# M906A.net
KiCad netlist of a schematic drawn in EAGLE
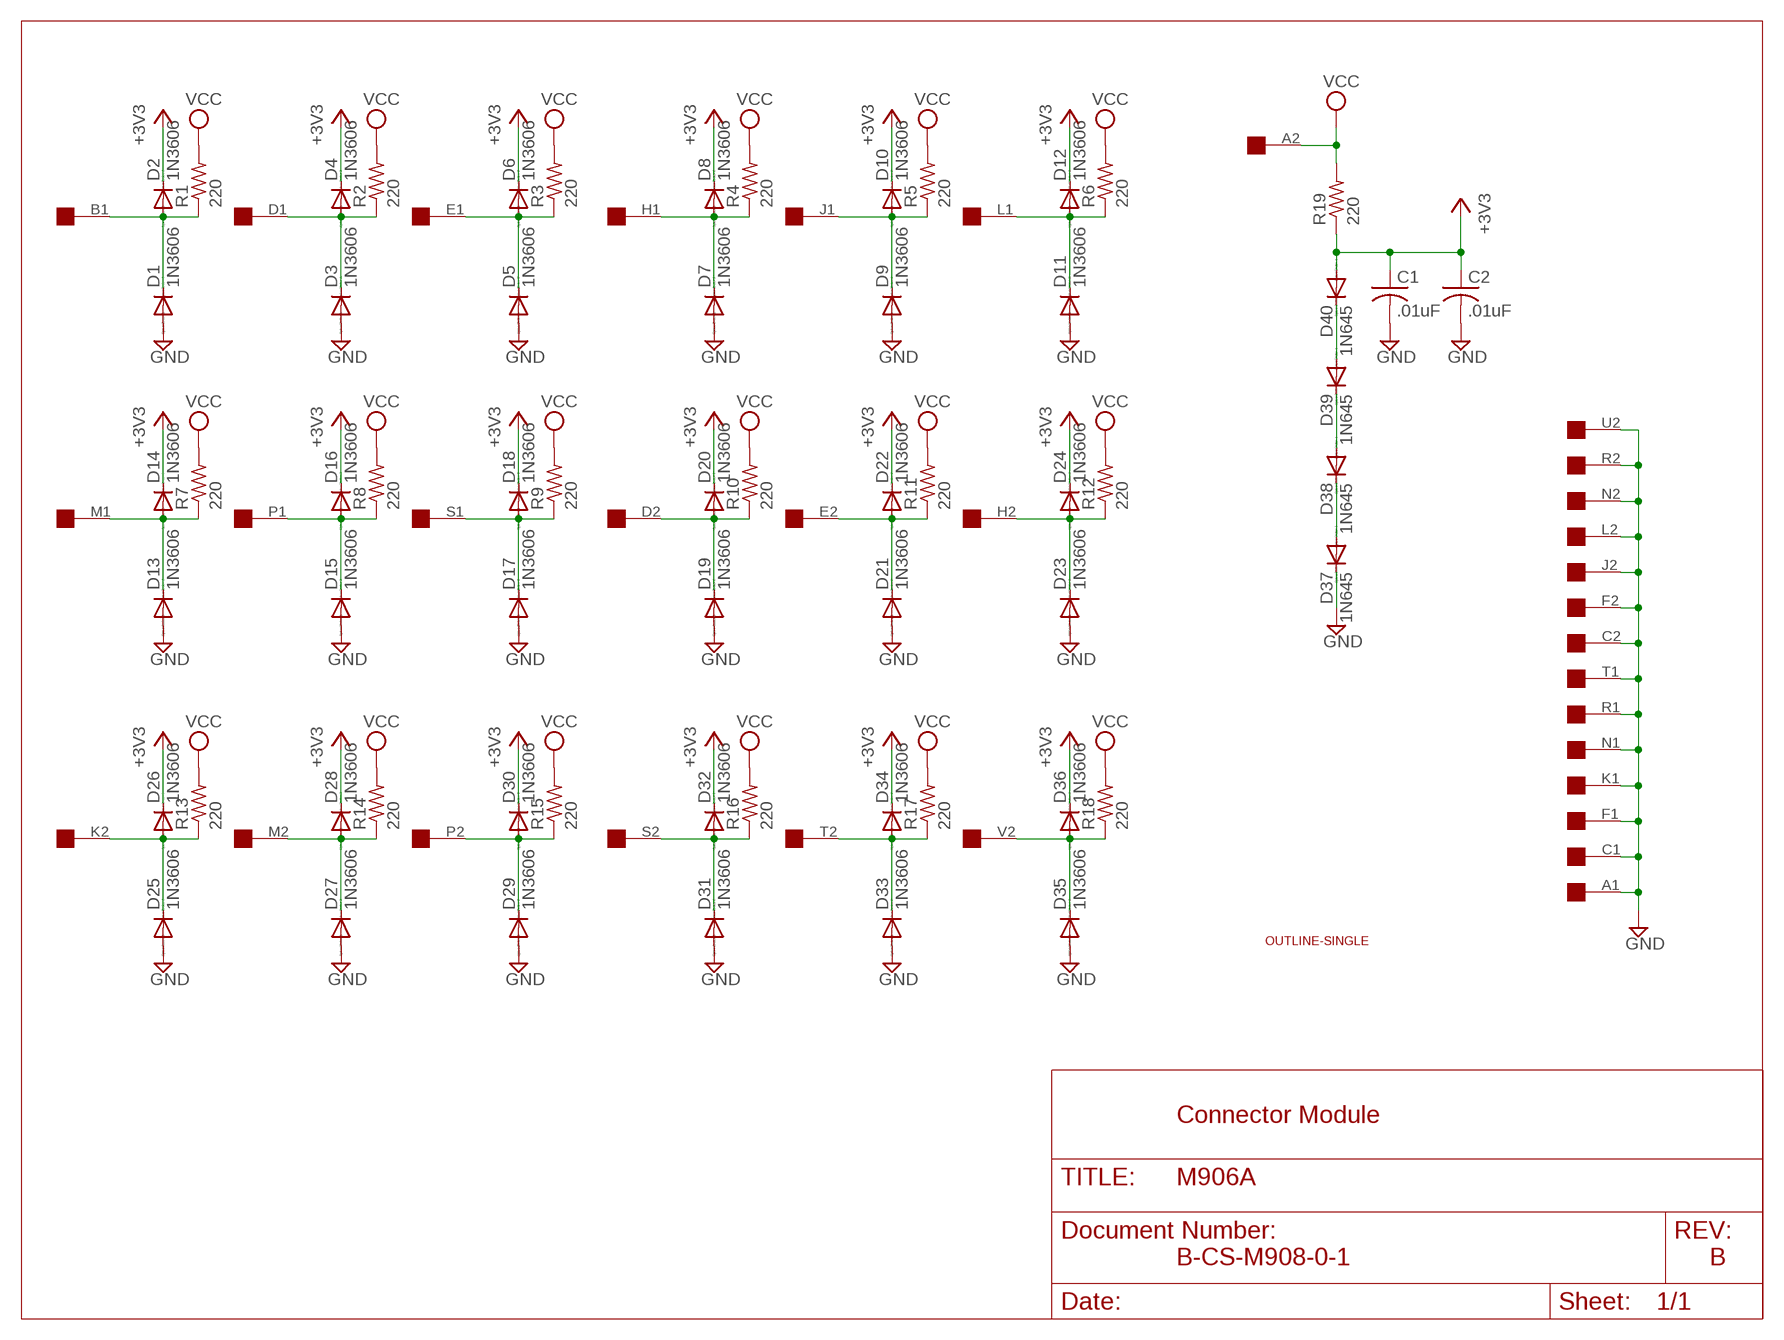
[diagram p0: schematic, sheet 1]

(export (version "E")
  (design (tool "Eeschema 10.0.6"))
  (components
    (comp (ref "C1")
      (value ".01uF")
      (footprint "eagle-import:C050-025X075")
      (libsource (lib "eagle-import") (part "C-US050-025X075"))
    )
    (comp (ref "C2")
      (value ".01uF")
      (footprint "eagle-import:C050-025X075")
      (libsource (lib "eagle-import") (part "C-US050-025X075"))
    )
    (comp (ref "D1")
      (value "1N3606")
      (footprint "eagle-import:DO35-10")
      (libsource (lib "eagle-import") (part "1N4148DO35-10"))
    )
    (comp (ref "D2")
      (value "1N3606")
      (footprint "eagle-import:DO35-10")
      (libsource (lib "eagle-import") (part "1N4148DO35-10"))
    )
    (comp (ref "D3")
      (value "1N3606")
      (footprint "eagle-import:DO35-10")
      (libsource (lib "eagle-import") (part "1N4148DO35-10"))
    )
    (comp (ref "D4")
      (value "1N3606")
      (footprint "eagle-import:DO35-10")
      (libsource (lib "eagle-import") (part "1N4148DO35-10"))
    )
    (comp (ref "D5")
      (value "1N3606")
      (footprint "eagle-import:DO35-10")
      (libsource (lib "eagle-import") (part "1N4148DO35-10"))
    )
    (comp (ref "D6")
      (value "1N3606")
      (footprint "eagle-import:DO35-10")
      (libsource (lib "eagle-import") (part "1N4148DO35-10"))
    )
    (comp (ref "D7")
      (value "1N3606")
      (footprint "eagle-import:DO35-10")
      (libsource (lib "eagle-import") (part "1N4148DO35-10"))
    )
    (comp (ref "D8")
      (value "1N3606")
      (footprint "eagle-import:DO35-10")
      (libsource (lib "eagle-import") (part "1N4148DO35-10"))
    )
    (comp (ref "D9")
      (value "1N3606")
      (footprint "eagle-import:DO35-10")
      (libsource (lib "eagle-import") (part "1N4148DO35-10"))
    )
    (comp (ref "D10")
      (value "1N3606")
      (footprint "eagle-import:DO35-10")
      (libsource (lib "eagle-import") (part "1N4148DO35-10"))
    )
    (comp (ref "D11")
      (value "1N3606")
      (footprint "eagle-import:DO35-10")
      (libsource (lib "eagle-import") (part "1N4148DO35-10"))
    )
    (comp (ref "D12")
      (value "1N3606")
      (footprint "eagle-import:DO35-10")
      (libsource (lib "eagle-import") (part "1N4148DO35-10"))
    )
    (comp (ref "D13")
      (value "1N3606")
      (footprint "eagle-import:DO35-10")
      (libsource (lib "eagle-import") (part "1N4148DO35-10"))
    )
    (comp (ref "D14")
      (value "1N3606")
      (footprint "eagle-import:DO35-10")
      (libsource (lib "eagle-import") (part "1N4148DO35-10"))
    )
    (comp (ref "D15")
      (value "1N3606")
      (footprint "eagle-import:DO35-10")
      (libsource (lib "eagle-import") (part "1N4148DO35-10"))
    )
    (comp (ref "D16")
      (value "1N3606")
      (footprint "eagle-import:DO35-10")
      (libsource (lib "eagle-import") (part "1N4148DO35-10"))
    )
    (comp (ref "D17")
      (value "1N3606")
      (footprint "eagle-import:DO35-10")
      (libsource (lib "eagle-import") (part "1N4148DO35-10"))
    )
    (comp (ref "D18")
      (value "1N3606")
      (footprint "eagle-import:DO35-10")
      (libsource (lib "eagle-import") (part "1N4148DO35-10"))
    )
    (comp (ref "D19")
      (value "1N3606")
      (footprint "eagle-import:DO35-10")
      (libsource (lib "eagle-import") (part "1N4148DO35-10"))
    )
    (comp (ref "D20")
      (value "1N3606")
      (footprint "eagle-import:DO35-10")
      (libsource (lib "eagle-import") (part "1N4148DO35-10"))
    )
    (comp (ref "D21")
      (value "1N3606")
      (footprint "eagle-import:DO35-10")
      (libsource (lib "eagle-import") (part "1N4148DO35-10"))
    )
    (comp (ref "D22")
      (value "1N3606")
      (footprint "eagle-import:DO35-10")
      (libsource (lib "eagle-import") (part "1N4148DO35-10"))
    )
    (comp (ref "D23")
      (value "1N3606")
      (footprint "eagle-import:DO35-10")
      (libsource (lib "eagle-import") (part "1N4148DO35-10"))
    )
    (comp (ref "D24")
      (value "1N3606")
      (footprint "eagle-import:DO35-10")
      (libsource (lib "eagle-import") (part "1N4148DO35-10"))
    )
    (comp (ref "D25")
      (value "1N3606")
      (footprint "eagle-import:DO35-10")
      (libsource (lib "eagle-import") (part "1N4148DO35-10"))
    )
    (comp (ref "D26")
      (value "1N3606")
      (footprint "eagle-import:DO35-10")
      (libsource (lib "eagle-import") (part "1N4148DO35-10"))
    )
    (comp (ref "D27")
      (value "1N3606")
      (footprint "eagle-import:DO35-10")
      (libsource (lib "eagle-import") (part "1N4148DO35-10"))
    )
    (comp (ref "D28")
      (value "1N3606")
      (footprint "eagle-import:DO35-10")
      (libsource (lib "eagle-import") (part "1N4148DO35-10"))
    )
    (comp (ref "D29")
      (value "1N3606")
      (footprint "eagle-import:DO35-10")
      (libsource (lib "eagle-import") (part "1N4148DO35-10"))
    )
    (comp (ref "D30")
      (value "1N3606")
      (footprint "eagle-import:DO35-10")
      (libsource (lib "eagle-import") (part "1N4148DO35-10"))
    )
    (comp (ref "D31")
      (value "1N3606")
      (footprint "eagle-import:DO35-10")
      (libsource (lib "eagle-import") (part "1N4148DO35-10"))
    )
    (comp (ref "D32")
      (value "1N3606")
      (footprint "eagle-import:DO35-10")
      (libsource (lib "eagle-import") (part "1N4148DO35-10"))
    )
    (comp (ref "D33")
      (value "1N3606")
      (footprint "eagle-import:DO35-10")
      (libsource (lib "eagle-import") (part "1N4148DO35-10"))
    )
    (comp (ref "D34")
      (value "1N3606")
      (footprint "eagle-import:DO35-10")
      (libsource (lib "eagle-import") (part "1N4148DO35-10"))
    )
    (comp (ref "D35")
      (value "1N3606")
      (footprint "eagle-import:DO35-10")
      (libsource (lib "eagle-import") (part "1N4148DO35-10"))
    )
    (comp (ref "D36")
      (value "1N3606")
      (footprint "eagle-import:DO35-10")
      (libsource (lib "eagle-import") (part "1N4148DO35-10"))
    )
    (comp (ref "D37")
      (value "1N645")
      (footprint "eagle-import:DO35-10")
      (libsource (lib "eagle-import") (part "1N4148DO35-10"))
    )
    (comp (ref "D38")
      (value "1N645")
      (footprint "eagle-import:DO35-10")
      (libsource (lib "eagle-import") (part "1N4148DO35-10"))
    )
    (comp (ref "D39")
      (value "1N645")
      (footprint "eagle-import:DO35-10")
      (libsource (lib "eagle-import") (part "1N4148DO35-10"))
    )
    (comp (ref "D40")
      (value "1N645")
      (footprint "eagle-import:DO35-10")
      (libsource (lib "eagle-import") (part "1N4148DO35-10"))
    )
    (comp (ref "R1")
      (value "220")
      (footprint "eagle-import:0207_10")
      (libsource (lib "eagle-import") (part "R-US_0207/10"))
    )
    (comp (ref "R2")
      (value "220")
      (footprint "eagle-import:0207_10")
      (libsource (lib "eagle-import") (part "R-US_0207/10"))
    )
    (comp (ref "R3")
      (value "220")
      (footprint "eagle-import:0207_10")
      (libsource (lib "eagle-import") (part "R-US_0207/10"))
    )
    (comp (ref "R4")
      (value "220")
      (footprint "eagle-import:0207_10")
      (libsource (lib "eagle-import") (part "R-US_0207/10"))
    )
    (comp (ref "R5")
      (value "220")
      (footprint "eagle-import:0207_10")
      (libsource (lib "eagle-import") (part "R-US_0207/10"))
    )
    (comp (ref "R6")
      (value "220")
      (footprint "eagle-import:0207_10")
      (libsource (lib "eagle-import") (part "R-US_0207/10"))
    )
    (comp (ref "R7")
      (value "220")
      (footprint "eagle-import:0207_10")
      (libsource (lib "eagle-import") (part "R-US_0207/10"))
    )
    (comp (ref "R8")
      (value "220")
      (footprint "eagle-import:0207_10")
      (libsource (lib "eagle-import") (part "R-US_0207/10"))
    )
    (comp (ref "R9")
      (value "220")
      (footprint "eagle-import:0207_10")
      (libsource (lib "eagle-import") (part "R-US_0207/10"))
    )
    (comp (ref "R10")
      (value "220")
      (footprint "eagle-import:0207_10")
      (libsource (lib "eagle-import") (part "R-US_0207/10"))
    )
    (comp (ref "R11")
      (value "220")
      (footprint "eagle-import:0207_10")
      (libsource (lib "eagle-import") (part "R-US_0207/10"))
    )
    (comp (ref "R12")
      (value "220")
      (footprint "eagle-import:0207_10")
      (libsource (lib "eagle-import") (part "R-US_0207/10"))
    )
    (comp (ref "R13")
      (value "220")
      (footprint "eagle-import:0207_10")
      (libsource (lib "eagle-import") (part "R-US_0207/10"))
    )
    (comp (ref "R14")
      (value "220")
      (footprint "eagle-import:0207_10")
      (libsource (lib "eagle-import") (part "R-US_0207/10"))
    )
    (comp (ref "R15")
      (value "220")
      (footprint "eagle-import:0207_10")
      (libsource (lib "eagle-import") (part "R-US_0207/10"))
    )
    (comp (ref "R16")
      (value "220")
      (footprint "eagle-import:0207_10")
      (libsource (lib "eagle-import") (part "R-US_0207/10"))
    )
    (comp (ref "R17")
      (value "220")
      (footprint "eagle-import:0207_10")
      (libsource (lib "eagle-import") (part "R-US_0207/10"))
    )
    (comp (ref "R18")
      (value "220")
      (footprint "eagle-import:0207_10")
      (libsource (lib "eagle-import") (part "R-US_0207/10"))
    )
    (comp (ref "R19")
      (value "220")
      (footprint "eagle-import:0207_10")
      (libsource (lib "eagle-import") (part "R-US_0207/10"))
    )
    (comp (ref "U$1")
      (value "SINGLE")
      (footprint "eagle-import:EDGE-CON2")
      (libsource (lib "eagle-import") (part "SINGLE"))
    )
    (comp (ref "U$2")
      (value "OUTLINE-SINGLE")
      (footprint "eagle-import:SINGLE")
      (libsource (lib "eagle-import") (part "OUTLINE-SINGLE"))
    )
  )
  (nets
    (net (code "1") (name "+3V3") (class "Default")
      (node (ref "C1") (pin "1") (pinfunction "1_1") (pintype "passive"))
      (node (ref "C2") (pin "1") (pinfunction "1_1") (pintype "passive"))
      (node (ref "D10") (pin "C") (pinfunction "C_C") (pintype "passive"))
      (node (ref "D12") (pin "C") (pinfunction "C_C") (pintype "passive"))
      (node (ref "D14") (pin "C") (pinfunction "C_C") (pintype "passive"))
      (node (ref "D16") (pin "C") (pinfunction "C_C") (pintype "passive"))
      (node (ref "D18") (pin "C") (pinfunction "C_C") (pintype "passive"))
      (node (ref "D2") (pin "C") (pinfunction "C_C") (pintype "passive"))
      (node (ref "D20") (pin "C") (pinfunction "C_C") (pintype "passive"))
      (node (ref "D22") (pin "C") (pinfunction "C_C") (pintype "passive"))
      (node (ref "D24") (pin "C") (pinfunction "C_C") (pintype "passive"))
      (node (ref "D26") (pin "C") (pinfunction "C_C") (pintype "passive"))
      (node (ref "D28") (pin "C") (pinfunction "C_C") (pintype "passive"))
      (node (ref "D30") (pin "C") (pinfunction "C_C") (pintype "passive"))
      (node (ref "D32") (pin "C") (pinfunction "C_C") (pintype "passive"))
      (node (ref "D34") (pin "C") (pinfunction "C_C") (pintype "passive"))
      (node (ref "D36") (pin "C") (pinfunction "C_C") (pintype "passive"))
      (node (ref "D4") (pin "C") (pinfunction "C_C") (pintype "passive"))
      (node (ref "D40") (pin "A") (pinfunction "A_A") (pintype "passive"))
      (node (ref "D6") (pin "C") (pinfunction "C_C") (pintype "passive"))
      (node (ref "D8") (pin "C") (pinfunction "C_C") (pintype "passive"))
      (node (ref "R19") (pin "1") (pinfunction "1_1") (pintype "passive"))
    )
    (net (code "2") (name "GND") (class "Default")
      (node (ref "C1") (pin "2") (pinfunction "2_2") (pintype "passive"))
      (node (ref "C2") (pin "2") (pinfunction "2_2") (pintype "passive"))
      (node (ref "D1") (pin "A") (pinfunction "A_A") (pintype "passive"))
      (node (ref "D11") (pin "A") (pinfunction "A_A") (pintype "passive"))
      (node (ref "D13") (pin "A") (pinfunction "A_A") (pintype "passive"))
      (node (ref "D15") (pin "A") (pinfunction "A_A") (pintype "passive"))
      (node (ref "D17") (pin "A") (pinfunction "A_A") (pintype "passive"))
      (node (ref "D19") (pin "A") (pinfunction "A_A") (pintype "passive"))
      (node (ref "D21") (pin "A") (pinfunction "A_A") (pintype "passive"))
      (node (ref "D23") (pin "A") (pinfunction "A_A") (pintype "passive"))
      (node (ref "D25") (pin "A") (pinfunction "A_A") (pintype "passive"))
      (node (ref "D27") (pin "A") (pinfunction "A_A") (pintype "passive"))
      (node (ref "D29") (pin "A") (pinfunction "A_A") (pintype "passive"))
      (node (ref "D3") (pin "A") (pinfunction "A_A") (pintype "passive"))
      (node (ref "D31") (pin "A") (pinfunction "A_A") (pintype "passive"))
      (node (ref "D33") (pin "A") (pinfunction "A_A") (pintype "passive"))
      (node (ref "D35") (pin "A") (pinfunction "A_A") (pintype "passive"))
      (node (ref "D37") (pin "C") (pinfunction "C_C") (pintype "passive"))
      (node (ref "D5") (pin "A") (pinfunction "A_A") (pintype "passive"))
      (node (ref "D7") (pin "A") (pinfunction "A_A") (pintype "passive"))
      (node (ref "D9") (pin "A") (pinfunction "A_A") (pintype "passive"))
      (node (ref "U$1") (pin "A1") (pinfunction "1_A1") (pintype "bidirectional"))
      (node (ref "U$1") (pin "C1") (pinfunction "1_C1") (pintype "bidirectional"))
      (node (ref "U$1") (pin "C2") (pinfunction "1_C2") (pintype "bidirectional"))
      (node (ref "U$1") (pin "F1") (pinfunction "1_F1") (pintype "bidirectional"))
      (node (ref "U$1") (pin "F2") (pinfunction "1_F2") (pintype "bidirectional"))
      (node (ref "U$1") (pin "J2") (pinfunction "1_J2") (pintype "bidirectional"))
      (node (ref "U$1") (pin "K1") (pinfunction "1_K1") (pintype "bidirectional"))
      (node (ref "U$1") (pin "L2") (pinfunction "1_L2") (pintype "bidirectional"))
      (node (ref "U$1") (pin "N1") (pinfunction "1_N1") (pintype "bidirectional"))
      (node (ref "U$1") (pin "N2") (pinfunction "1_N2") (pintype "bidirectional"))
      (node (ref "U$1") (pin "R1") (pinfunction "1_R1") (pintype "bidirectional"))
      (node (ref "U$1") (pin "R2") (pinfunction "1_R2") (pintype "bidirectional"))
      (node (ref "U$1") (pin "T1") (pinfunction "1_T1") (pintype "bidirectional"))
      (node (ref "U$1") (pin "U2") (pinfunction "1_U2") (pintype "bidirectional"))
    )
    (net (code "3") (name "Net-(D37-PadA)") (class "Default")
      (node (ref "D37") (pin "A") (pinfunction "A_A") (pintype "passive"))
      (node (ref "D38") (pin "C") (pinfunction "C_C") (pintype "passive"))
    )
    (net (code "4") (name "Net-(D38-PadA)") (class "Default")
      (node (ref "D38") (pin "A") (pinfunction "A_A") (pintype "passive"))
      (node (ref "D39") (pin "C") (pinfunction "C_C") (pintype "passive"))
    )
    (net (code "5") (name "Net-(D39-PadA)") (class "Default")
      (node (ref "D39") (pin "A") (pinfunction "A_A") (pintype "passive"))
      (node (ref "D40") (pin "C") (pinfunction "C_C") (pintype "passive"))
    )
    (net (code "6") (name "Net-(U$1AC-1)") (class "Default")
      (node (ref "D17") (pin "C") (pinfunction "C_C") (pintype "passive"))
      (node (ref "D18") (pin "A") (pinfunction "A_A") (pintype "passive"))
      (node (ref "R9") (pin "1") (pinfunction "1_1") (pintype "passive"))
      (node (ref "U$1") (pin "S1") (pinfunction "1_S1") (pintype "bidirectional"))
    )
    (net (code "7") (name "Net-(U$1AD-1)") (class "Default")
      (node (ref "D31") (pin "C") (pinfunction "C_C") (pintype "passive"))
      (node (ref "D32") (pin "A") (pinfunction "A_A") (pintype "passive"))
      (node (ref "R16") (pin "1") (pinfunction "1_1") (pintype "passive"))
      (node (ref "U$1") (pin "S2") (pinfunction "1_S2") (pintype "bidirectional"))
    )
    (net (code "8") (name "Net-(U$1AF-1)") (class "Default")
      (node (ref "D33") (pin "C") (pinfunction "C_C") (pintype "passive"))
      (node (ref "D34") (pin "A") (pinfunction "A_A") (pintype "passive"))
      (node (ref "R17") (pin "1") (pinfunction "1_1") (pintype "passive"))
      (node (ref "U$1") (pin "T2") (pinfunction "1_T2") (pintype "bidirectional"))
    )
    (net (code "9") (name "Net-(U$1AJ-1)") (class "Default")
      (node (ref "D35") (pin "C") (pinfunction "C_C") (pintype "passive"))
      (node (ref "D36") (pin "A") (pinfunction "A_A") (pintype "passive"))
      (node (ref "R18") (pin "1") (pinfunction "1_1") (pintype "passive"))
      (node (ref "U$1") (pin "V2") (pinfunction "1_V2") (pintype "bidirectional"))
    )
    (net (code "10") (name "Net-(U$1C-1)") (class "Default")
      (node (ref "D1") (pin "C") (pinfunction "C_C") (pintype "passive"))
      (node (ref "D2") (pin "A") (pinfunction "A_A") (pintype "passive"))
      (node (ref "R1") (pin "1") (pinfunction "1_1") (pintype "passive"))
      (node (ref "U$1") (pin "B1") (pinfunction "1_B1") (pintype "bidirectional"))
    )
    (net (code "11") (name "Net-(U$1G-1)") (class "Default")
      (node (ref "D3") (pin "C") (pinfunction "C_C") (pintype "passive"))
      (node (ref "D4") (pin "A") (pinfunction "A_A") (pintype "passive"))
      (node (ref "R2") (pin "1") (pinfunction "1_1") (pintype "passive"))
      (node (ref "U$1") (pin "D1") (pinfunction "1_D1") (pintype "bidirectional"))
    )
    (net (code "12") (name "Net-(U$1H-1)") (class "Default")
      (node (ref "D19") (pin "C") (pinfunction "C_C") (pintype "passive"))
      (node (ref "D20") (pin "A") (pinfunction "A_A") (pintype "passive"))
      (node (ref "R10") (pin "1") (pinfunction "1_1") (pintype "passive"))
      (node (ref "U$1") (pin "D2") (pinfunction "1_D2") (pintype "bidirectional"))
    )
    (net (code "13") (name "Net-(U$1I-1)") (class "Default")
      (node (ref "D5") (pin "C") (pinfunction "C_C") (pintype "passive"))
      (node (ref "D6") (pin "A") (pinfunction "A_A") (pintype "passive"))
      (node (ref "R3") (pin "1") (pinfunction "1_1") (pintype "passive"))
      (node (ref "U$1") (pin "E1") (pinfunction "1_E1") (pintype "bidirectional"))
    )
    (net (code "14") (name "Net-(U$1J-1)") (class "Default")
      (node (ref "D21") (pin "C") (pinfunction "C_C") (pintype "passive"))
      (node (ref "D22") (pin "A") (pinfunction "A_A") (pintype "passive"))
      (node (ref "R11") (pin "1") (pinfunction "1_1") (pintype "passive"))
      (node (ref "U$1") (pin "E2") (pinfunction "1_E2") (pintype "bidirectional"))
    )
    (net (code "15") (name "Net-(U$1M-1)") (class "Default")
      (node (ref "D7") (pin "C") (pinfunction "C_C") (pintype "passive"))
      (node (ref "D8") (pin "A") (pinfunction "A_A") (pintype "passive"))
      (node (ref "R4") (pin "1") (pinfunction "1_1") (pintype "passive"))
      (node (ref "U$1") (pin "H1") (pinfunction "1_H1") (pintype "bidirectional"))
    )
    (net (code "16") (name "Net-(U$1N-1)") (class "Default")
      (node (ref "D23") (pin "C") (pinfunction "C_C") (pintype "passive"))
      (node (ref "D24") (pin "A") (pinfunction "A_A") (pintype "passive"))
      (node (ref "R12") (pin "1") (pinfunction "1_1") (pintype "passive"))
      (node (ref "U$1") (pin "H2") (pinfunction "1_H2") (pintype "bidirectional"))
    )
    (net (code "17") (name "Net-(U$1O-1)") (class "Default")
      (node (ref "D10") (pin "A") (pinfunction "A_A") (pintype "passive"))
      (node (ref "D9") (pin "C") (pinfunction "C_C") (pintype "passive"))
      (node (ref "R5") (pin "1") (pinfunction "1_1") (pintype "passive"))
      (node (ref "U$1") (pin "J1") (pinfunction "1_J1") (pintype "bidirectional"))
    )
    (net (code "18") (name "Net-(U$1R-1)") (class "Default")
      (node (ref "D25") (pin "C") (pinfunction "C_C") (pintype "passive"))
      (node (ref "D26") (pin "A") (pinfunction "A_A") (pintype "passive"))
      (node (ref "R13") (pin "1") (pinfunction "1_1") (pintype "passive"))
      (node (ref "U$1") (pin "K2") (pinfunction "1_K2") (pintype "bidirectional"))
    )
    (net (code "19") (name "Net-(U$1S-1)") (class "Default")
      (node (ref "D11") (pin "C") (pinfunction "C_C") (pintype "passive"))
      (node (ref "D12") (pin "A") (pinfunction "A_A") (pintype "passive"))
      (node (ref "R6") (pin "1") (pinfunction "1_1") (pintype "passive"))
      (node (ref "U$1") (pin "L1") (pinfunction "1_L1") (pintype "bidirectional"))
    )
    (net (code "20") (name "Net-(U$1U-1)") (class "Default")
      (node (ref "D13") (pin "C") (pinfunction "C_C") (pintype "passive"))
      (node (ref "D14") (pin "A") (pinfunction "A_A") (pintype "passive"))
      (node (ref "R7") (pin "1") (pinfunction "1_1") (pintype "passive"))
      (node (ref "U$1") (pin "M1") (pinfunction "1_M1") (pintype "bidirectional"))
    )
    (net (code "21") (name "Net-(U$1V-1)") (class "Default")
      (node (ref "D27") (pin "C") (pinfunction "C_C") (pintype "passive"))
      (node (ref "D28") (pin "A") (pinfunction "A_A") (pintype "passive"))
      (node (ref "R14") (pin "1") (pinfunction "1_1") (pintype "passive"))
      (node (ref "U$1") (pin "M2") (pinfunction "1_M2") (pintype "bidirectional"))
    )
    (net (code "22") (name "Net-(U$1Y-1)") (class "Default")
      (node (ref "D15") (pin "C") (pinfunction "C_C") (pintype "passive"))
      (node (ref "D16") (pin "A") (pinfunction "A_A") (pintype "passive"))
      (node (ref "R8") (pin "1") (pinfunction "1_1") (pintype "passive"))
      (node (ref "U$1") (pin "P1") (pinfunction "1_P1") (pintype "bidirectional"))
    )
    (net (code "23") (name "Net-(U$1Z-1)") (class "Default")
      (node (ref "D29") (pin "C") (pinfunction "C_C") (pintype "passive"))
      (node (ref "D30") (pin "A") (pinfunction "A_A") (pintype "passive"))
      (node (ref "R15") (pin "1") (pinfunction "1_1") (pintype "passive"))
      (node (ref "U$1") (pin "P2") (pinfunction "1_P2") (pintype "bidirectional"))
    )
    (net (code "24") (name "VCC") (class "Default")
      (node (ref "R1") (pin "2") (pinfunction "2_2") (pintype "passive"))
      (node (ref "R10") (pin "2") (pinfunction "2_2") (pintype "passive"))
      (node (ref "R11") (pin "2") (pinfunction "2_2") (pintype "passive"))
      (node (ref "R12") (pin "2") (pinfunction "2_2") (pintype "passive"))
      (node (ref "R13") (pin "2") (pinfunction "2_2") (pintype "passive"))
      (node (ref "R14") (pin "2") (pinfunction "2_2") (pintype "passive"))
      (node (ref "R15") (pin "2") (pinfunction "2_2") (pintype "passive"))
      (node (ref "R16") (pin "2") (pinfunction "2_2") (pintype "passive"))
      (node (ref "R17") (pin "2") (pinfunction "2_2") (pintype "passive"))
      (node (ref "R18") (pin "2") (pinfunction "2_2") (pintype "passive"))
      (node (ref "R19") (pin "2") (pinfunction "2_2") (pintype "passive"))
      (node (ref "R2") (pin "2") (pinfunction "2_2") (pintype "passive"))
      (node (ref "R3") (pin "2") (pinfunction "2_2") (pintype "passive"))
      (node (ref "R4") (pin "2") (pinfunction "2_2") (pintype "passive"))
      (node (ref "R5") (pin "2") (pinfunction "2_2") (pintype "passive"))
      (node (ref "R6") (pin "2") (pinfunction "2_2") (pintype "passive"))
      (node (ref "R7") (pin "2") (pinfunction "2_2") (pintype "passive"))
      (node (ref "R8") (pin "2") (pinfunction "2_2") (pintype "passive"))
      (node (ref "R9") (pin "2") (pinfunction "2_2") (pintype "passive"))
      (node (ref "U$1") (pin "A2") (pinfunction "1_A2") (pintype "bidirectional"))
    )
  )
)
